# Psyduck.net
KiCad netlist of a schematic drawn in Altium Designer
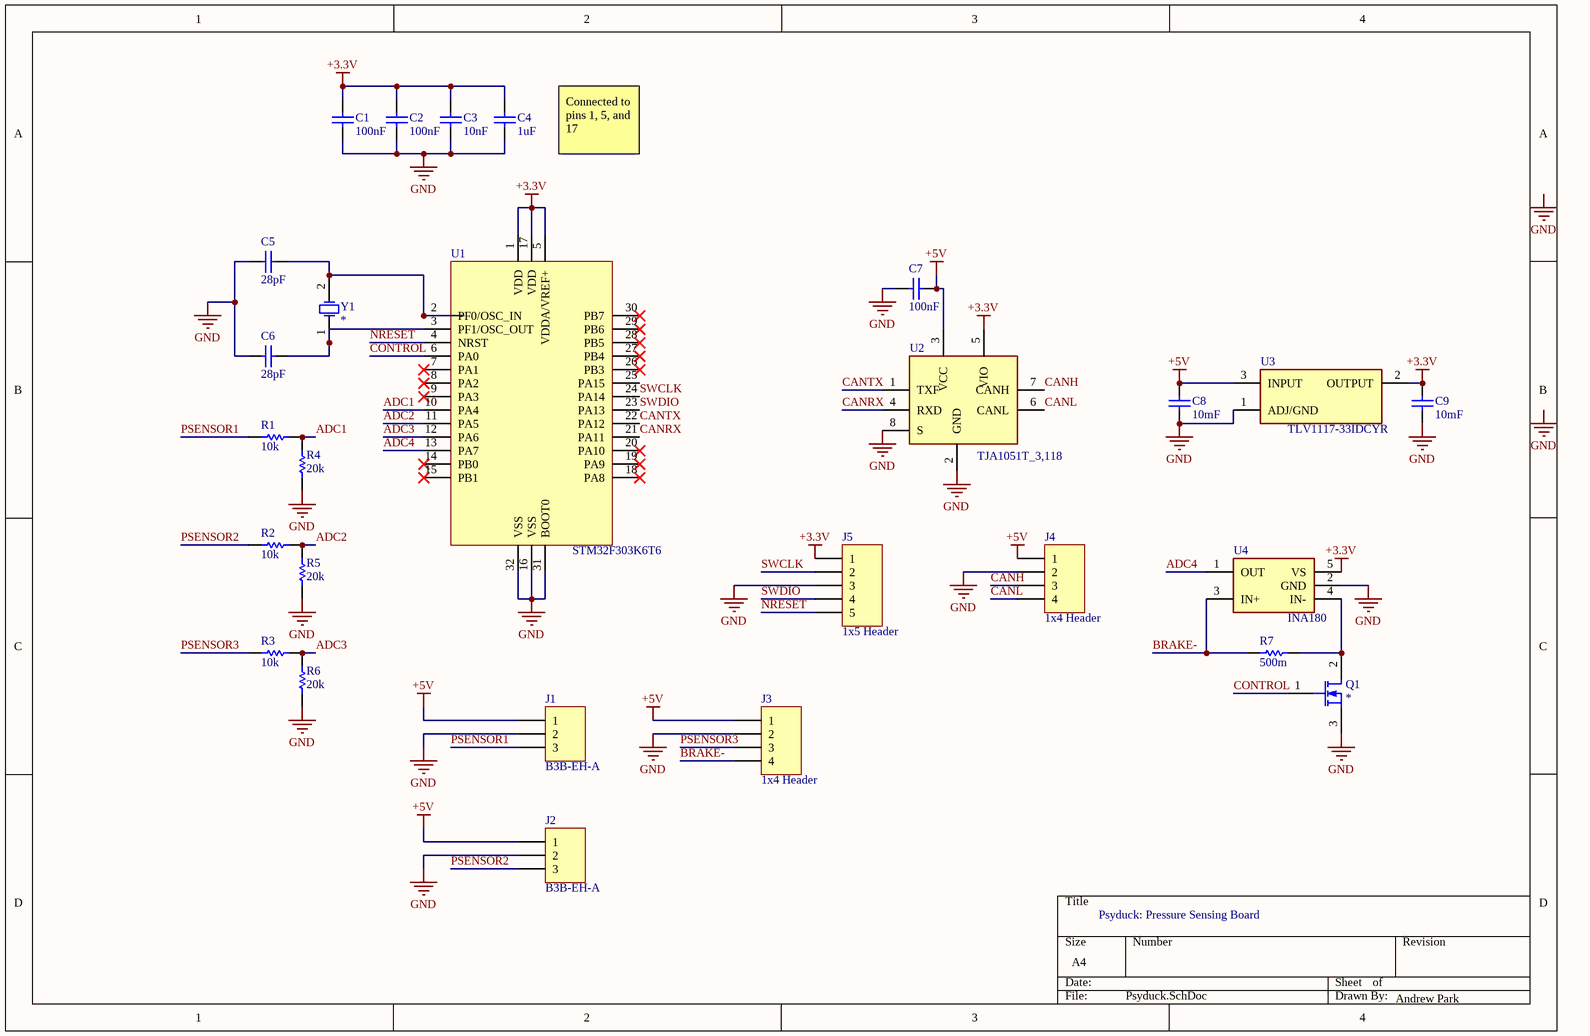
[diagram p0: Psyduck.SchDoc]

(export (version "E")
  (design (tool "Eeschema 10.0.6"))
  (components
    (comp (ref "C1")
      (value "100nF")
      (footprint "0805 - Capacitor")
      (description "Nonpolarized Capacitor")
      (fields (field (name "Comment") "Capacitor - Nonpolarized"))
      (libsource (lib "General") (part "Capacitor - Nonpolarized"))
    )
    (comp (ref "C2")
      (value "100nF")
      (footprint "0805 - Capacitor")
      (description "Nonpolarized Capacitor")
      (fields (field (name "Comment") "Capacitor - Nonpolarized"))
      (libsource (lib "General") (part "Capacitor - Nonpolarized"))
    )
    (comp (ref "C3")
      (value "10nF")
      (footprint "0805 - Capacitor")
      (description "Nonpolarized Capacitor")
      (fields (field (name "Comment") "Capacitor - Nonpolarized"))
      (libsource (lib "General") (part "Capacitor - Nonpolarized"))
    )
    (comp (ref "C4")
      (value "1uF")
      (footprint "0805 - Capacitor")
      (description "Nonpolarized Capacitor")
      (fields (field (name "Comment") "Capacitor - Nonpolarized"))
      (libsource (lib "General") (part "Capacitor - Nonpolarized"))
    )
    (comp (ref "C5")
      (value "28pF")
      (footprint "0805 - Capacitor")
      (description "Nonpolarized Capacitor")
      (fields (field (name "Comment") "Capacitor - Nonpolarized"))
      (libsource (lib "General") (part "Capacitor - Nonpolarized"))
    )
    (comp (ref "C6")
      (value "28pF")
      (footprint "0805 - Capacitor")
      (description "Nonpolarized Capacitor")
      (fields (field (name "Comment") "Capacitor - Nonpolarized"))
      (libsource (lib "General") (part "Capacitor - Nonpolarized"))
    )
    (comp (ref "C7")
      (value "100nF")
      (footprint "0805 - Capacitor")
      (description "Nonpolarized Capacitor")
      (fields (field (name "Comment") "Capacitor - Nonpolarized"))
      (libsource (lib "General") (part "Capacitor - Nonpolarized"))
    )
    (comp (ref "C8")
      (value "10mF")
      (footprint "0805 - Capacitor")
      (description "Nonpolarized Capacitor")
      (fields (field (name "Comment") "Capacitor - Nonpolarized"))
      (libsource (lib "General") (part "Capacitor - Nonpolarized"))
    )
    (comp (ref "C9")
      (value "10mF")
      (footprint "0805 - Capacitor")
      (description "Nonpolarized Capacitor")
      (fields (field (name "Comment") "Capacitor - Nonpolarized"))
      (libsource (lib "General") (part "Capacitor - Nonpolarized"))
    )
    (comp (ref "J1")
      (value "B3B-EH-A")
      (footprint "B3B-XH")
      (description "1x3 Pin Header")
      (libsource (lib "GeneralConnectors") (part "1x3 Header"))
    )
    (comp (ref "J2")
      (value "B3B-EH-A")
      (footprint "B3B-XH")
      (description "1x3 Pin Header")
      (libsource (lib "GeneralConnectors") (part "1x3 Header"))
    )
    (comp (ref "J3")
      (value "1x4 Header")
      (footprint "B4B-XH")
      (description "1x4 Pin Header")
      (libsource (lib "GeneralConnectors") (part "1x4 Header"))
    )
    (comp (ref "J4")
      (value "1x4 Header")
      (footprint "B4B-XH")
      (description "1x4 Pin Header")
      (libsource (lib "GeneralConnectors") (part "1x4 Header"))
    )
    (comp (ref "J5")
      (value "1x5 Header")
      (footprint "HDR1X5")
      (description "1x5 Pin Header")
      (libsource (lib "GeneralConnectors") (part "1x5 Header"))
    )
    (comp (ref "Q1")
      (value "MOSFET-N")
      (footprint "SC70/SOT323")
      (description "N-Channel MOSFET")
      (fields (field (name "ALTIUM_VALUE") "*"))
      (libsource (lib "General") (part "MOSFET-N"))
    )
    (comp (ref "R1")
      (value "10k")
      (footprint "0603 - Resistor")
      (description "Resistor")
      (libsource (lib "General") (part "Resistor"))
    )
    (comp (ref "R2")
      (value "10k")
      (footprint "0603 - Resistor")
      (description "Resistor")
      (libsource (lib "General") (part "Resistor"))
    )
    (comp (ref "R3")
      (value "10k")
      (footprint "0603 - Resistor")
      (description "Resistor")
      (libsource (lib "General") (part "Resistor"))
    )
    (comp (ref "R4")
      (value "20k")
      (footprint "0603 - Resistor")
      (description "Resistor")
      (libsource (lib "General") (part "Resistor"))
    )
    (comp (ref "R5")
      (value "20k")
      (footprint "0603 - Resistor")
      (description "Resistor")
      (libsource (lib "General") (part "Resistor"))
    )
    (comp (ref "R6")
      (value "20k")
      (footprint "0603 - Resistor")
      (description "Resistor")
      (libsource (lib "General") (part "Resistor"))
    )
    (comp (ref "R7")
      (value "500m")
      (footprint "0603 - Resistor")
      (description "Resistor")
      (libsource (lib "General") (part "Resistor"))
    )
    (comp (ref "U1")
      (value "STM32F303K6T6")
      (footprint "QFP80P900X900X160-32N")
      (description "Integrated Circuit")
      (libsource (lib "Embedded") (part "STM32F303K6T6"))
    )
    (comp (ref "U2")
      (value "TJA1051T_3,118")
      (footprint "TJA1051T/3,118")
      (description "CAN Transceiver IC 4.5V-5.5V 250ns")
      (fields (field (name "MANUFACTURER") "NXP") (field (name "MANUFACTURER PART NUMBER") "TJA1051T/3,118"))
      (libsource (lib "GeneralComponents") (part "TJA1051T_3,118"))
    )
    (comp (ref "U3")
      (value "TLV1117-33IDCYR")
      (footprint "TLV1117")
      (description "Linear Voltage Regulator IC 3.3V 800MA SOT223-4")
      (fields (field (name "MANUFACTURER") "Texas Instruments"))
      (libsource (lib "GeneralComponents") (part "TLV1117-33IDCYR"))
    )
    (comp (ref "U4")
      (value "INA180")
      (footprint "INA180")
      (description "0V to 26V Current Sense Amplifier")
      (fields
        (field (name "MANUFACTURER") "Texas Instruments")
        (field (name "MANUFACTURER PART NUMBER") "INA180A2IDBVR")
      )
      (libsource (lib "GeneralComponents") (part "INA180"))
    )
    (comp (ref "Y1")
      (value "Oscillator")
      (footprint "2-SMD NO LEAD CRSYSTAL")
      (description "Crystal Oscillator")
      (fields (field (name "ALTIUM_VALUE") "*"))
      (libsource (lib "General") (part "Oscillator"))
    )
  )
  (nets
    (net (code "1") (name "+3.3V") (class "Default")
      (node (ref "C1") (pin "2") (pinfunction "2_2") (pintype "passive"))
      (node (ref "C2") (pin "2") (pinfunction "2_2") (pintype "passive"))
      (node (ref "C3") (pin "2") (pinfunction "2_2") (pintype "passive"))
      (node (ref "C4") (pin "2") (pinfunction "2_2") (pintype "passive"))
      (node (ref "C9") (pin "2") (pinfunction "2_2") (pintype "passive"))
      (node (ref "J5") (pin "1") (pinfunction "1_1") (pintype "passive"))
      (node (ref "U1") (pin "1") (pinfunction "VDD_1") (pintype "passive"))
      (node (ref "U1") (pin "17") (pinfunction "VDD_17") (pintype "passive"))
      (node (ref "U1") (pin "5") (pinfunction "VDDA/VREF+_5") (pintype "passive"))
      (node (ref "U2") (pin "5") (pinfunction "VIO_5") (pintype "passive"))
      (node (ref "U3") (pin "2") (pinfunction "OUTPUT_2") (pintype "passive"))
      (node (ref "U4") (pin "5") (pinfunction "VS_5") (pintype "passive"))
    )
    (net (code "2") (name "+5V") (class "Default")
      (node (ref "C7") (pin "2") (pinfunction "2_2") (pintype "passive"))
      (node (ref "C8") (pin "2") (pinfunction "2_2") (pintype "passive"))
      (node (ref "J1") (pin "1") (pinfunction "1_1") (pintype "passive"))
      (node (ref "J2") (pin "1") (pinfunction "1_1") (pintype "passive"))
      (node (ref "J3") (pin "1") (pinfunction "1_1") (pintype "passive"))
      (node (ref "J4") (pin "1") (pinfunction "1_1") (pintype "passive"))
      (node (ref "U2") (pin "3") (pinfunction "VCC_3") (pintype "passive"))
      (node (ref "U3") (pin "3") (pinfunction "INPUT_3") (pintype "passive"))
    )
    (net (code "3") (name "/ADC1") (class "Default")
      (node (ref "R1") (pin "2") (pinfunction "2_2") (pintype "passive"))
      (node (ref "R4") (pin "2") (pinfunction "2_2") (pintype "passive"))
      (node (ref "U1") (pin "10") (pinfunction "PA4_10") (pintype "passive"))
    )
    (net (code "4") (name "/ADC2") (class "Default")
      (node (ref "R2") (pin "2") (pinfunction "2_2") (pintype "passive"))
      (node (ref "R5") (pin "2") (pinfunction "2_2") (pintype "passive"))
      (node (ref "U1") (pin "11") (pinfunction "PA5_11") (pintype "passive"))
    )
    (net (code "5") (name "/ADC3") (class "Default")
      (node (ref "R3") (pin "2") (pinfunction "2_2") (pintype "passive"))
      (node (ref "R6") (pin "2") (pinfunction "2_2") (pintype "passive"))
      (node (ref "U1") (pin "12") (pinfunction "PA6_12") (pintype "passive"))
    )
    (net (code "6") (name "/ADC4") (class "Default")
      (node (ref "U1") (pin "13") (pinfunction "PA7_13") (pintype "passive"))
      (node (ref "U4") (pin "1") (pinfunction "OUT_1") (pintype "passive"))
    )
    (net (code "7") (name "/BRAKE-") (class "Default")
      (node (ref "J3") (pin "4") (pinfunction "4_4") (pintype "passive"))
      (node (ref "R7") (pin "2") (pinfunction "2_2") (pintype "passive"))
      (node (ref "U4") (pin "3") (pinfunction "IN+_3") (pintype "passive"))
    )
    (net (code "8") (name "/CANH") (class "Default")
      (node (ref "J4") (pin "3") (pinfunction "3_3") (pintype "passive"))
      (node (ref "U2") (pin "7") (pinfunction "CANH_7") (pintype "passive"))
    )
    (net (code "9") (name "/CANL") (class "Default")
      (node (ref "J4") (pin "4") (pinfunction "4_4") (pintype "passive"))
      (node (ref "U2") (pin "6") (pinfunction "CANL_6") (pintype "passive"))
    )
    (net (code "10") (name "/CANRX") (class "Default")
      (node (ref "U1") (pin "21") (pinfunction "PA11_21") (pintype "passive"))
      (node (ref "U2") (pin "4") (pinfunction "RXD_4") (pintype "passive"))
    )
    (net (code "11") (name "/CANTX") (class "Default")
      (node (ref "U1") (pin "22") (pinfunction "PA12_22") (pintype "passive"))
      (node (ref "U2") (pin "1") (pinfunction "TXF_1") (pintype "passive"))
    )
    (net (code "12") (name "/CONTROL") (class "Default")
      (node (ref "Q1") (pin "1") (pinfunction "G_1") (pintype "passive"))
      (node (ref "U1") (pin "6") (pinfunction "PA0_6") (pintype "passive"))
    )
    (net (code "13") (name "/NRESET") (class "Default")
      (node (ref "J5") (pin "5") (pinfunction "5_5") (pintype "passive"))
      (node (ref "U1") (pin "4") (pinfunction "NRST_4") (pintype "passive"))
    )
    (net (code "14") (name "/PSENSOR1") (class "Default")
      (node (ref "J1") (pin "3") (pinfunction "3_3") (pintype "passive"))
      (node (ref "R1") (pin "1") (pinfunction "1_1") (pintype "passive"))
    )
    (net (code "15") (name "/PSENSOR2") (class "Default")
      (node (ref "J2") (pin "3") (pinfunction "3_3") (pintype "passive"))
      (node (ref "R2") (pin "1") (pinfunction "1_1") (pintype "passive"))
    )
    (net (code "16") (name "/PSENSOR3") (class "Default")
      (node (ref "J3") (pin "3") (pinfunction "3_3") (pintype "passive"))
      (node (ref "R3") (pin "1") (pinfunction "1_1") (pintype "passive"))
    )
    (net (code "17") (name "/SWCLK") (class "Default")
      (node (ref "J5") (pin "2") (pinfunction "2_2") (pintype "passive"))
      (node (ref "U1") (pin "24") (pinfunction "PA14_24") (pintype "passive"))
    )
    (net (code "18") (name "/SWDIO") (class "Default")
      (node (ref "J5") (pin "4") (pinfunction "4_4") (pintype "passive"))
      (node (ref "U1") (pin "23") (pinfunction "PA13_23") (pintype "passive"))
    )
    (net (code "19") (name "GND") (class "Default")
      (node (ref "C1") (pin "1") (pinfunction "1_1") (pintype "passive"))
      (node (ref "C2") (pin "1") (pinfunction "1_1") (pintype "passive"))
      (node (ref "C3") (pin "1") (pinfunction "1_1") (pintype "passive"))
      (node (ref "C4") (pin "1") (pinfunction "1_1") (pintype "passive"))
      (node (ref "C5") (pin "1") (pinfunction "1_1") (pintype "passive"))
      (node (ref "C6") (pin "1") (pinfunction "1_1") (pintype "passive"))
      (node (ref "C7") (pin "1") (pinfunction "1_1") (pintype "passive"))
      (node (ref "C8") (pin "1") (pinfunction "1_1") (pintype "passive"))
      (node (ref "C9") (pin "1") (pinfunction "1_1") (pintype "passive"))
      (node (ref "J1") (pin "2") (pinfunction "2_2") (pintype "passive"))
      (node (ref "J2") (pin "2") (pinfunction "2_2") (pintype "passive"))
      (node (ref "J3") (pin "2") (pinfunction "2_2") (pintype "passive"))
      (node (ref "J4") (pin "2") (pinfunction "2_2") (pintype "passive"))
      (node (ref "J5") (pin "3") (pinfunction "3_3") (pintype "passive"))
      (node (ref "Q1") (pin "3") (pinfunction "S_3") (pintype "passive"))
      (node (ref "R4") (pin "1") (pinfunction "1_1") (pintype "passive"))
      (node (ref "R5") (pin "1") (pinfunction "1_1") (pintype "passive"))
      (node (ref "R6") (pin "1") (pinfunction "1_1") (pintype "passive"))
      (node (ref "U1") (pin "16") (pinfunction "VSS_16") (pintype "passive"))
      (node (ref "U1") (pin "31") (pinfunction "BOOT0_31") (pintype "passive"))
      (node (ref "U1") (pin "32") (pinfunction "VSS_32") (pintype "passive"))
      (node (ref "U2") (pin "2") (pinfunction "GND_2") (pintype "passive"))
      (node (ref "U2") (pin "8") (pinfunction "S_8") (pintype "passive"))
      (node (ref "U3") (pin "1") (pinfunction "ADJ/GND_1") (pintype "passive"))
      (node (ref "U4") (pin "2") (pinfunction "GND_2") (pintype "passive"))
    )
    (net (code "20") (name "Net-(Q1-D)") (class "Default")
      (node (ref "Q1") (pin "2") (pinfunction "D_2") (pintype "passive"))
      (node (ref "R7") (pin "1") (pinfunction "1_1") (pintype "passive"))
      (node (ref "U4") (pin "4") (pinfunction "IN-_4") (pintype "passive"))
    )
    (net (code "21") (name "Net-(U1-PF0{slash}OSC_IN)") (class "Default")
      (node (ref "C5") (pin "2") (pinfunction "2_2") (pintype "passive"))
      (node (ref "U1") (pin "2") (pinfunction "PF0/OSC_IN_2") (pintype "passive"))
      (node (ref "Y1") (pin "2") (pinfunction "OSC2_2") (pintype "passive"))
    )
    (net (code "22") (name "Net-(U1-PF1{slash}OSC_OUT)") (class "Default")
      (node (ref "C6") (pin "2") (pinfunction "2_2") (pintype "passive"))
      (node (ref "U1") (pin "3") (pinfunction "PF1/OSC_OUT_3") (pintype "passive"))
      (node (ref "Y1") (pin "1") (pinfunction "OSC1_1") (pintype "passive"))
    )
    (net (code "23") (name "unconnected-(U1-PA1-Pad7)") (class "Default")
      (node (ref "U1") (pin "7") (pinfunction "PA1_7") (pintype "passive+no_connect"))
    )
    (net (code "24") (name "unconnected-(U1-PA2-Pad8)") (class "Default")
      (node (ref "U1") (pin "8") (pinfunction "PA2_8") (pintype "passive+no_connect"))
    )
    (net (code "25") (name "unconnected-(U1-PA3-Pad9)") (class "Default")
      (node (ref "U1") (pin "9") (pinfunction "PA3_9") (pintype "passive+no_connect"))
    )
    (net (code "26") (name "unconnected-(U1-PA8-Pad18)") (class "Default")
      (node (ref "U1") (pin "18") (pinfunction "PA8_18") (pintype "passive+no_connect"))
    )
    (net (code "27") (name "unconnected-(U1-PA9-Pad19)") (class "Default")
      (node (ref "U1") (pin "19") (pinfunction "PA9_19") (pintype "passive+no_connect"))
    )
    (net (code "28") (name "unconnected-(U1-PA10-Pad20)") (class "Default")
      (node (ref "U1") (pin "20") (pinfunction "PA10_20") (pintype "passive+no_connect"))
    )
    (net (code "29") (name "unconnected-(U1-PA15-Pad25)") (class "Default")
      (node (ref "U1") (pin "25") (pinfunction "PA15_25") (pintype "passive"))
    )
    (net (code "30") (name "unconnected-(U1-PB0-Pad14)") (class "Default")
      (node (ref "U1") (pin "14") (pinfunction "PB0_14") (pintype "passive+no_connect"))
    )
    (net (code "31") (name "unconnected-(U1-PB1-Pad15)") (class "Default")
      (node (ref "U1") (pin "15") (pinfunction "PB1_15") (pintype "passive+no_connect"))
    )
    (net (code "32") (name "unconnected-(U1-PB3-Pad26)") (class "Default")
      (node (ref "U1") (pin "26") (pinfunction "PB3_26") (pintype "passive+no_connect"))
    )
    (net (code "33") (name "unconnected-(U1-PB4-Pad27)") (class "Default")
      (node (ref "U1") (pin "27") (pinfunction "PB4_27") (pintype "passive+no_connect"))
    )
    (net (code "34") (name "unconnected-(U1-PB5-Pad28)") (class "Default")
      (node (ref "U1") (pin "28") (pinfunction "PB5_28") (pintype "passive+no_connect"))
    )
    (net (code "35") (name "unconnected-(U1-PB6-Pad29)") (class "Default")
      (node (ref "U1") (pin "29") (pinfunction "PB6_29") (pintype "passive+no_connect"))
    )
    (net (code "36") (name "unconnected-(U1-PB7-Pad30)") (class "Default")
      (node (ref "U1") (pin "30") (pinfunction "PB7_30") (pintype "passive+no_connect"))
    )
  )
)
